# Viper12A_SMPS_12V_2A_V1.net
KiCad netlist of a schematic drawn in Altium Designer
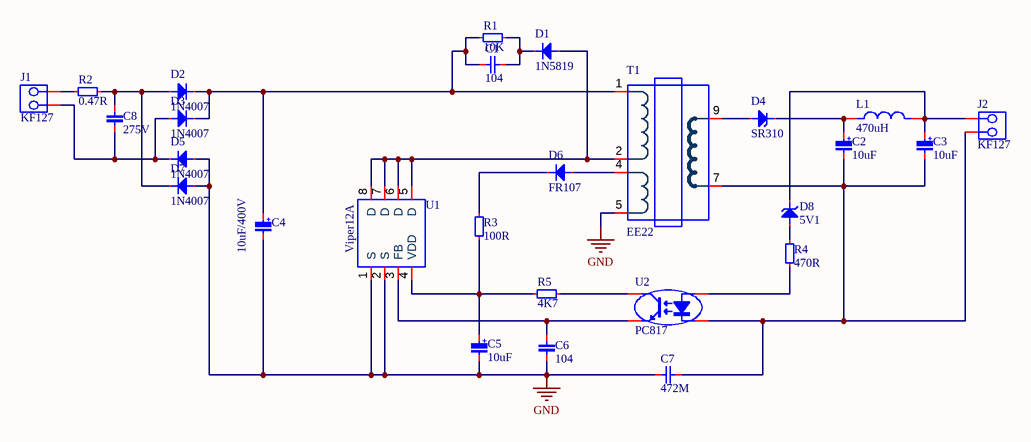
[diagram p0: Viper12A_SMPS_12V_2A_V1.SchDoc]

(export (version "E")
  (design (tool "Eeschema 10.0.6"))
  (components
    (comp (ref "C1")
      (value "104")
      (footprint "CAP_DISC_4x3_YL")
      (libsource (lib "MyAltiumLibrary") (part "Capacitors(Disc)"))
    )
    (comp (ref "C2")
      (value "10uF")
      (footprint "CAP_RAD_3.5mm")
      (libsource (lib "MyAltiumLibrary") (part "Capacitor(Radian)"))
    )
    (comp (ref "C3")
      (value "10uF")
      (footprint "CAP_RAD_3.5mm")
      (libsource (lib "MyAltiumLibrary") (part "Capacitor(Radian)"))
    )
    (comp (ref "C4")
      (value "10uF/400V")
      (footprint "CAP_RAD_D10x12.5_POL_BK")
      (libsource (lib "MyAltiumLibrary") (part "Capacitor(Radian)"))
    )
    (comp (ref "C5")
      (value "10uF")
      (footprint "CAP_RAD_2.5mm")
      (libsource (lib "MyAltiumLibrary") (part "Capacitor(Radian)"))
    )
    (comp (ref "C6")
      (value "104")
      (footprint "CAP_Ceramic_Disc_2")
      (libsource (lib "") (part "Capacitors(Disc)_1"))
    )
    (comp (ref "C7")
      (value "472M")
      (footprint "CAP_DISC_Y2222")
      (libsource (lib "MyAltiumLibrary") (part "Capacitors(Disc)"))
    )
    (comp (ref "C8")
      (value "275V")
      (footprint "CAP_BOX_13x4x7_BL")
      (libsource (lib "MyAltiumLibrary") (part "Capacitors(film)"))
    )
    (comp (ref "D1")
      (value "1N5819")
      (footprint "DO-204AL-BK")
      (description "1A - Schotky Diode")
      (libsource (lib "MyAltiumLibrary") (part "Diode-1N5819"))
    )
    (comp (ref "D2")
      (value "1N4007")
      (footprint "DO-204AL-BK")
      (libsource (lib "MyAltiumLibrary") (part "Diode-1N4007"))
    )
    (comp (ref "D3")
      (value "1N4007")
      (footprint "DO-204AL-BK")
      (libsource (lib "MyAltiumLibrary") (part "Diode-1N4007"))
    )
    (comp (ref "D4")
      (value "SR310")
      (footprint "DO-201AD-R-BK")
      (description "3A-Schotky")
      (libsource (lib "MyAltiumLibrary") (part "Diode-SR310"))
    )
    (comp (ref "D5")
      (value "1N4007")
      (footprint "DO-204AL-BK")
      (libsource (lib "MyAltiumLibrary") (part "Diode-1N4007"))
    )
    (comp (ref "D6")
      (value "FR107")
      (footprint "DO-204AL-BK")
      (libsource (lib "MyAltiumLibrary") (part "Diode-1N4007"))
    )
    (comp (ref "D7")
      (value "1N4007")
      (footprint "DO-204AL-BK")
      (libsource (lib "MyAltiumLibrary") (part "Diode-1N4007"))
    )
    (comp (ref "D8")
      (value "5V1")
      (footprint "DO-204AL-RD")
      (libsource (lib "MyAltiumLibrary") (part "Diode-Zener"))
    )
    (comp (ref "J1")
      (value "KF127")
      (footprint "DG127-5.0-02P-14-00AH")
      (libsource (lib "MyAltiumLibrary") (part "DG127-5.0-02P-14-00AH"))
    )
    (comp (ref "J2")
      (value "KF127")
      (footprint "DG127-5.0-02P-14-00AH")
      (libsource (lib "") (part "DG127-5.0-02P-14-00AH_1"))
    )
    (comp (ref "L1")
      (value "470uH")
      (footprint "RLB0712_vertical")
      (libsource (lib "MyAltiumLibrary") (part "Inductors"))
    )
    (comp (ref "R1") (value "10K") (footprint "RES-0.5W-H") (libsource (lib "") (part "Resistors THD_1")))
    (comp (ref "R2") (value "0.47R") (footprint "RES-0.5W-H") (libsource (lib "") (part "Resistors THD_1")))
    (comp (ref "R3")
      (value "100R")
      (footprint "RES-0.25W-H")
      (libsource (lib "MyAltiumLibrary") (part "Resistors THD"))
    )
    (comp (ref "R4")
      (value "470R")
      (footprint "RES-0.25W-H")
      (libsource (lib "MyAltiumLibrary") (part "Resistors THD"))
    )
    (comp (ref "R5") (value "4K7") (footprint "RES-0.25W-H") (libsource (lib "") (part "Resistors THD_1")))
    (comp (ref "T1")
      (value "EE22")
      (footprint "TRANSFORMER-EE22-VERTICAL(5+5)")
      (libsource (lib "MyAltiumLibrary") (part "TRANS-EE22-18-6-VERTICAL(5+5)"))
    )
    (comp (ref "U1")
      (value "Viper12A")
      (footprint "DIP-8")
      (libsource (lib "MyAltiumLibrary") (part "SMPS-Viper12A"))
    )
    (comp (ref "U2")
      (value "PC817")
      (footprint "PC817-DIP")
      (libsource (lib "MyAltiumLibrary") (part "Opto-PC817"))
    )
  )
  (nets
    (net (code "1") (name "GND") (class "Default")
      (node (ref "C4") (pin "2") (pinfunction "2_2") (pintype "passive"))
      (node (ref "C5") (pin "2") (pinfunction "2_2") (pintype "passive"))
      (node (ref "C6") (pin "1") (pinfunction "1_1") (pintype "passive"))
      (node (ref "C7") (pin "1") (pinfunction "1_1") (pintype "passive"))
      (node (ref "D5") (pin "1") (pinfunction "1_1") (pintype "passive"))
      (node (ref "D7") (pin "1") (pinfunction "1_1") (pintype "passive"))
      (node (ref "T1") (pin "5") (pinfunction "5_5") (pintype "passive"))
      (node (ref "U1") (pin "1") (pinfunction "S_1") (pintype "passive"))
      (node (ref "U1") (pin "2") (pinfunction "S_2") (pintype "passive"))
    )
    (net (code "2") (name "Net-(C1-Pad1)") (class "Default")
      (node (ref "C1") (pin "1") (pinfunction "1_1") (pintype "passive"))
      (node (ref "C4") (pin "1") (pinfunction "1_1") (pintype "passive"))
      (node (ref "D2") (pin "2") (pinfunction "2_2") (pintype "passive"))
      (node (ref "D3") (pin "2") (pinfunction "2_2") (pintype "passive"))
      (node (ref "R1") (pin "2") (pinfunction "2_2") (pintype "passive"))
      (node (ref "T1") (pin "1") (pinfunction "1_1") (pintype "passive"))
    )
    (net (code "3") (name "Net-(C1-Pad2)") (class "Default")
      (node (ref "C1") (pin "2") (pinfunction "2_2") (pintype "passive"))
      (node (ref "D1") (pin "2") (pinfunction "2_2") (pintype "passive"))
      (node (ref "R1") (pin "1") (pinfunction "1_1") (pintype "passive"))
    )
    (net (code "4") (name "Net-(C2-Pad1)") (class "Default")
      (node (ref "C2") (pin "1") (pinfunction "1_1") (pintype "passive"))
      (node (ref "D4") (pin "2") (pinfunction "2_2") (pintype "passive"))
      (node (ref "L1") (pin "1") (pinfunction "1_1") (pintype "passive"))
    )
    (net (code "5") (name "Net-(C3-Pad1)") (class "Default")
      (node (ref "C3") (pin "1") (pinfunction "1_1") (pintype "passive"))
      (node (ref "D8") (pin "2") (pinfunction "2_2") (pintype "passive"))
      (node (ref "J2") (pin "2") (pinfunction "2_2") (pintype "passive"))
      (node (ref "L1") (pin "2") (pinfunction "2_2") (pintype "passive"))
    )
    (net (code "6") (name "Net-(C8-Pad1)") (class "Default")
      (node (ref "C8") (pin "1") (pinfunction "1_1") (pintype "passive"))
      (node (ref "D3") (pin "1") (pinfunction "1_1") (pintype "passive"))
      (node (ref "D5") (pin "2") (pinfunction "2_2") (pintype "passive"))
      (node (ref "J1") (pin "1") (pinfunction "1_1") (pintype "passive"))
    )
    (net (code "7") (name "Net-(C8-Pad2)") (class "Default")
      (node (ref "C8") (pin "2") (pinfunction "2_2") (pintype "passive"))
      (node (ref "D2") (pin "1") (pinfunction "1_1") (pintype "passive"))
      (node (ref "D7") (pin "2") (pinfunction "2_2") (pintype "passive"))
      (node (ref "R2") (pin "1") (pinfunction "1_1") (pintype "passive"))
    )
    (net (code "8") (name "Net-(D1-Pad1)") (class "Default")
      (node (ref "D1") (pin "1") (pinfunction "1_1") (pintype "passive"))
      (node (ref "T1") (pin "2") (pinfunction "2_2") (pintype "passive"))
      (node (ref "U1") (pin "5") (pinfunction "D_5") (pintype "passive"))
      (node (ref "U1") (pin "6") (pinfunction "D_6") (pintype "passive"))
      (node (ref "U1") (pin "7") (pinfunction "D_7") (pintype "passive"))
      (node (ref "U1") (pin "8") (pinfunction "D_8") (pintype "passive"))
    )
    (net (code "9") (name "Net-(D4-Pad1)") (class "Default")
      (node (ref "D4") (pin "1") (pinfunction "1_1") (pintype "passive"))
      (node (ref "T1") (pin "9") (pinfunction "9_9") (pintype "passive"))
    )
    (net (code "10") (name "Net-(D6-Pad1)") (class "Default")
      (node (ref "D6") (pin "1") (pinfunction "1_1") (pintype "passive"))
      (node (ref "T1") (pin "4") (pinfunction "4_4") (pintype "passive"))
    )
    (net (code "11") (name "Net-(D6-Pad2)") (class "Default")
      (node (ref "D6") (pin "2") (pinfunction "2_2") (pintype "passive"))
      (node (ref "R3") (pin "2") (pinfunction "2_2") (pintype "passive"))
    )
    (net (code "12") (name "Net-(D8-Pad1)") (class "Default")
      (node (ref "D8") (pin "1") (pinfunction "1_1") (pintype "passive"))
      (node (ref "R4") (pin "2") (pinfunction "2_2") (pintype "passive"))
    )
    (net (code "13") (name "Net-(J1-Pad2)") (class "Default")
      (node (ref "J1") (pin "2") (pinfunction "2_2") (pintype "passive"))
      (node (ref "R2") (pin "2") (pinfunction "2_2") (pintype "passive"))
    )
    (net (code "14") (name "Net-(U1-FB)") (class "Default")
      (node (ref "C6") (pin "2") (pinfunction "2_2") (pintype "passive"))
      (node (ref "U1") (pin "3") (pinfunction "FB_3") (pintype "passive"))
      (node (ref "U2") (pin "3") (pinfunction "E_3") (pintype "passive"))
    )
    (net (code "15") (name "Net-(U1-VDD)") (class "Default")
      (node (ref "C5") (pin "1") (pinfunction "1_1") (pintype "passive"))
      (node (ref "R3") (pin "1") (pinfunction "1_1") (pintype "passive"))
      (node (ref "R5") (pin "2") (pinfunction "2_2") (pintype "passive"))
      (node (ref "U1") (pin "4") (pinfunction "VDD_4") (pintype "passive"))
    )
    (net (code "16") (name "Net-(U2-A)") (class "Default")
      (node (ref "R4") (pin "1") (pinfunction "1_1") (pintype "passive"))
      (node (ref "U2") (pin "1") (pinfunction "A_1") (pintype "passive"))
    )
    (net (code "17") (name "Net-(U2-C)") (class "Default")
      (node (ref "R5") (pin "1") (pinfunction "1_1") (pintype "passive"))
      (node (ref "U2") (pin "4") (pinfunction "C_4") (pintype "passive"))
    )
    (net (code "18") (name "Net-(U2-K)") (class "Default")
      (node (ref "C2") (pin "2") (pinfunction "2_2") (pintype "passive"))
      (node (ref "C3") (pin "2") (pinfunction "2_2") (pintype "passive"))
      (node (ref "C7") (pin "2") (pinfunction "2_2") (pintype "passive"))
      (node (ref "J2") (pin "1") (pinfunction "1_1") (pintype "passive"))
      (node (ref "T1") (pin "7") (pinfunction "7_7") (pintype "passive"))
      (node (ref "U2") (pin "2") (pinfunction "K_2") (pintype "passive"))
    )
  )
)
